# LEDboard.net
KiCad netlist of a schematic drawn in EAGLE
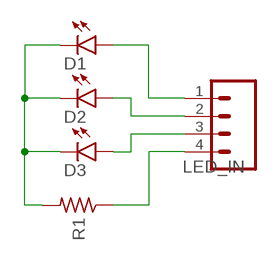
[diagram p0: schematic, sheet 1]

(export (version "E")
  (design (tool "Eeschema 10.0.6"))
  (components
    (comp (ref "D1")
      (value "LED5MM")
      (footprint "eagle-import:LED5MM")
      (libsource (lib "eagle-import") (part "LED5MM"))
    )
    (comp (ref "D2")
      (value "LED5MM")
      (footprint "eagle-import:LED5MM")
      (libsource (lib "eagle-import") (part "LED5MM"))
    )
    (comp (ref "D3")
      (value "LED5MM")
      (footprint "eagle-import:LED5MM")
      (libsource (lib "eagle-import") (part "LED5MM"))
    )
    (comp (ref "LED_IN")
      (value "M04")
      (footprint "eagle-import:04P")
      (libsource (lib "eagle-import") (part "M04"))
    )
    (comp (ref "R1")
      (value "R-US_0204/7")
      (footprint "eagle-import:0204_7")
      (libsource (lib "eagle-import") (part "R-US_0204/7"))
    )
  )
  (nets
    (net (code "1") (name "Net-(D1-C)") (class "Default")
      (node (ref "D1") (pin "K") (pinfunction "C_K") (pintype "passive"))
      (node (ref "D2") (pin "K") (pinfunction "C_K") (pintype "passive"))
      (node (ref "D3") (pin "K") (pinfunction "C_K") (pintype "passive"))
      (node (ref "R1") (pin "2") (pinfunction "2_2") (pintype "passive"))
    )
    (net (code "2") (name "Net-(D1-PadA)") (class "Default")
      (node (ref "D1") (pin "A") (pinfunction "A_A") (pintype "passive"))
      (node (ref "LED_IN") (pin "1") (pinfunction "1_1") (pintype "passive"))
    )
    (net (code "3") (name "Net-(D2-PadA)") (class "Default")
      (node (ref "D2") (pin "A") (pinfunction "A_A") (pintype "passive"))
      (node (ref "LED_IN") (pin "2") (pinfunction "2_2") (pintype "passive"))
    )
    (net (code "4") (name "Net-(D3-PadA)") (class "Default")
      (node (ref "D3") (pin "A") (pinfunction "A_A") (pintype "passive"))
      (node (ref "LED_IN") (pin "3") (pinfunction "3_3") (pintype "passive"))
    )
    (net (code "5") (name "Net-(LED_IN-Pad4)") (class "Default")
      (node (ref "LED_IN") (pin "4") (pinfunction "4_4") (pintype "passive"))
      (node (ref "R1") (pin "1") (pinfunction "1_1") (pintype "passive"))
    )
  )
)
